# Mirtle_Teensy3_ESP_2016_Hotec6c.net
KiCad netlist of a schematic drawn in EAGLE
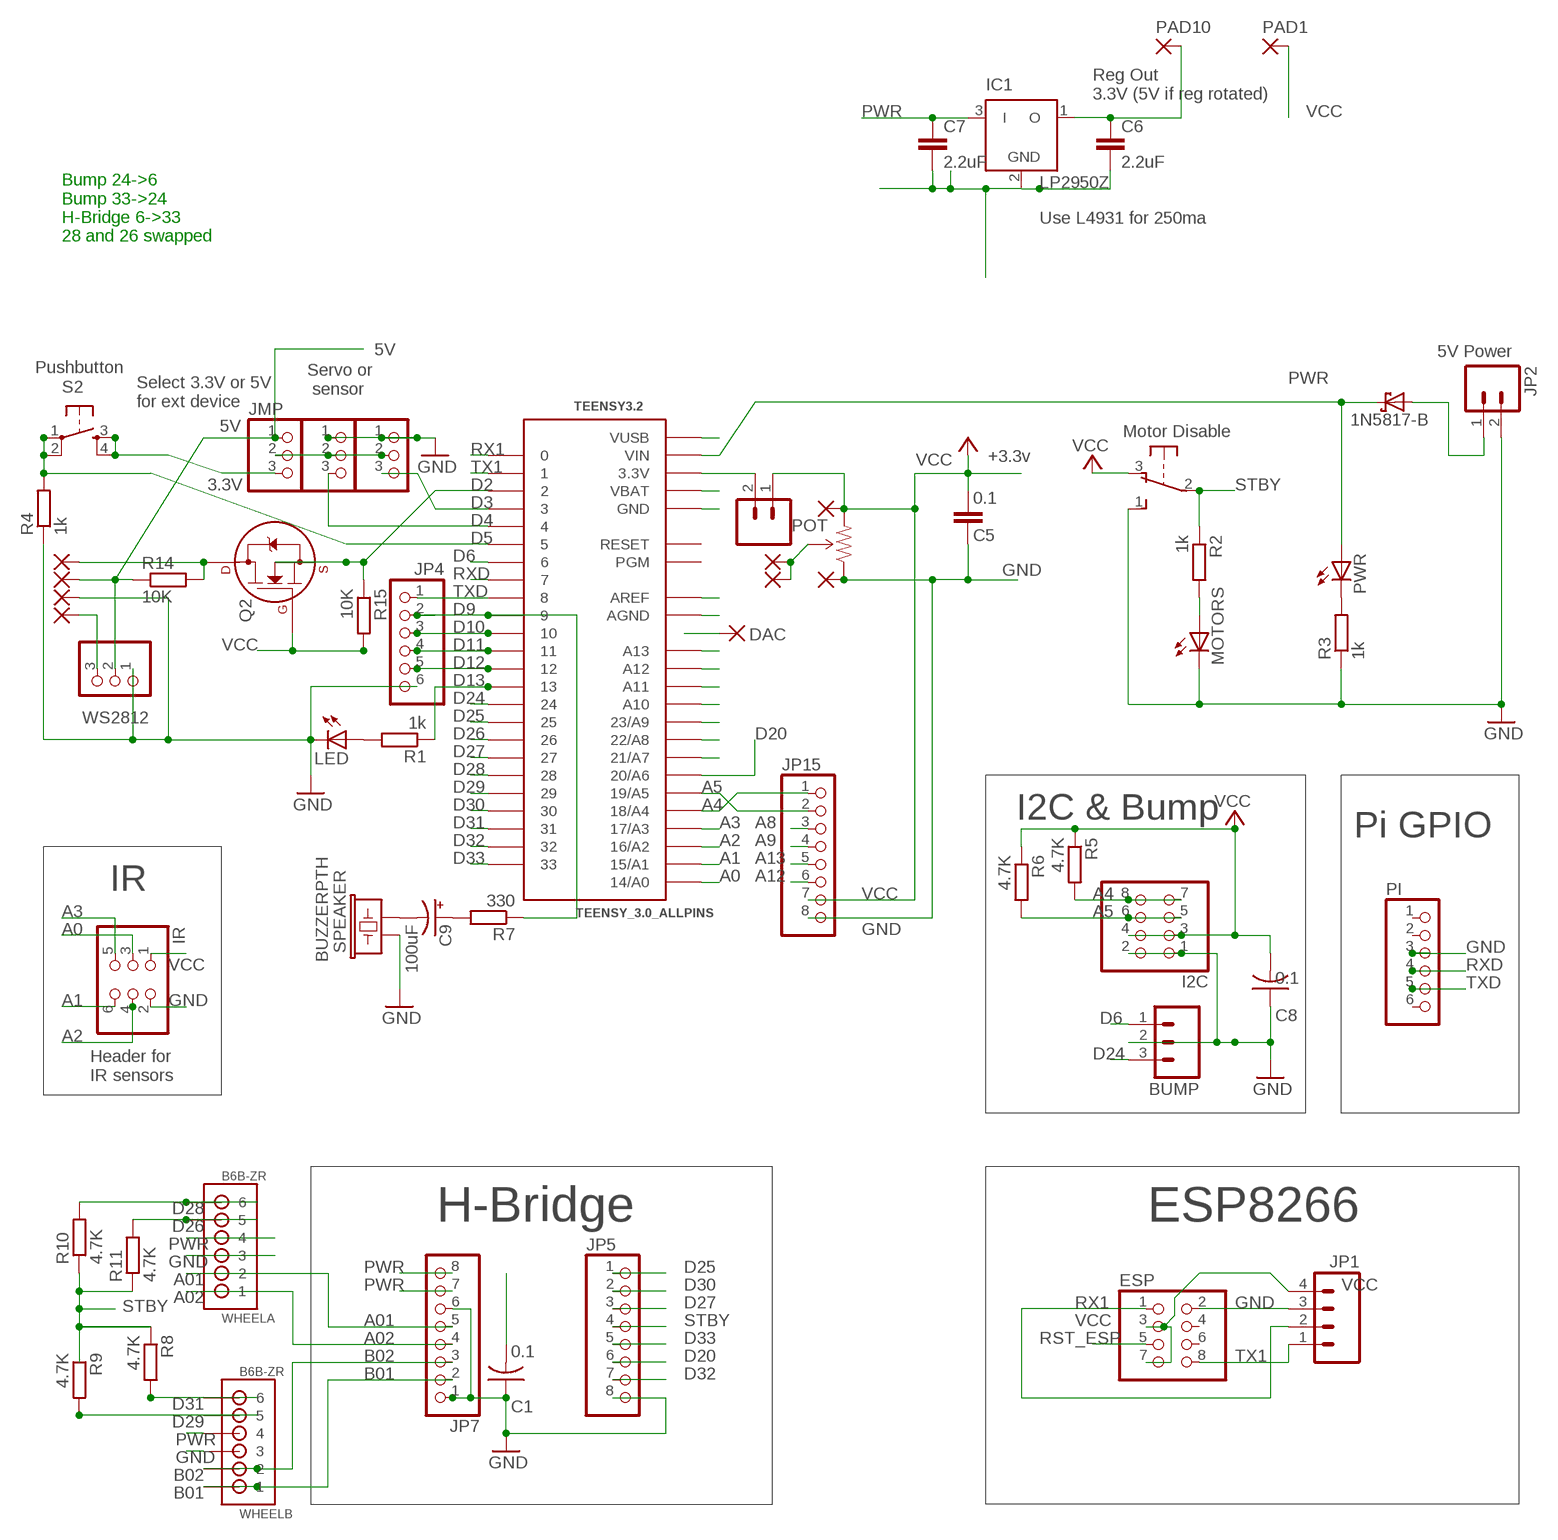
[diagram p0: schematic, sheet 1]

(export (version "E")
  (design (tool "Eeschema 10.0.6"))
  (components
    (comp (ref "3V3")
      (value "M02PTH")
      (footprint "eagle-import:1X02")
      (libsource (lib "eagle-import") (part "M02PTH"))
    )
    (comp (ref "BUMP")
      (value "M03SCREW")
      (footprint "eagle-import:SCREWTERMINAL-3.5MM-3")
      (libsource (lib "eagle-import") (part "M03SCREW"))
    )
    (comp (ref "C1")
      (value "0.1")
      (footprint "eagle-import:C025-024X044")
      (libsource (lib "eagle-import") (part "C-US025-024X044"))
    )
    (comp (ref "C5")
      (value "0.1")
      (footprint "eagle-import:CAP-PTH-SMALLEZ")
      (libsource (lib "eagle-import") (part "CAPEZ"))
    )
    (comp (ref "C6")
      (value "2.2uF")
      (footprint "eagle-import:C050-024X044")
      (libsource (lib "eagle-import") (part "C-EU050-024X044"))
    )
    (comp (ref "C7")
      (value "2.2uF")
      (footprint "eagle-import:C050-024X044")
      (libsource (lib "eagle-import") (part "C-EU050-024X044"))
    )
    (comp (ref "C8")
      (value "0.1")
      (footprint "eagle-import:C025-024X044")
      (libsource (lib "eagle-import") (part "C-US025-024X044"))
    )
    (comp (ref "C9")
      (value "100uF")
      (footprint "eagle-import:E2,5-5")
      (libsource (lib "eagle-import") (part "CPOL-USE2.5-5"))
    )
    (comp (ref "D1")
      (value "1N5817-B")
      (footprint "eagle-import:DO41-7.6")
      (libsource (lib "eagle-import") (part "1N5817-B"))
    )
    (comp (ref "DAC")
      (value "1,6/0,8")
      (footprint "eagle-import:1,6_0,8")
      (libsource (lib "eagle-import") (part "1,6/0,8"))
    )
    (comp (ref "ESP")
      (value "PINHD-2X4")
      (footprint "eagle-import:2X04")
      (libsource (lib "eagle-import") (part "adafruit_mem_PINHD-2X4"))
    )
    (comp (ref "EXT")
      (value "PINHD-1X3")
      (footprint "eagle-import:1X03")
      (libsource (lib "eagle-import") (part "PINHD-1X3"))
    )
    (comp (ref "EXT1")
      (value "PINHD-1X3")
      (footprint "eagle-import:1X03")
      (libsource (lib "eagle-import") (part "PINHD-1X3"))
    )
    (comp (ref "I2C")
      (value "PINHD-2X4")
      (footprint "eagle-import:2X04")
      (libsource (lib "eagle-import") (part "PINHD-2X4"))
    )
    (comp (ref "IC1")
      (value "LP2950Z")
      (footprint "eagle-import:TO92")
      (libsource (lib "eagle-import") (part "LP2950Z"))
    )
    (comp (ref "IR")
      (value "PINHD-2X3")
      (footprint "eagle-import:2X03")
      (libsource (lib "eagle-import") (part "PINHD-2X3"))
    )
    (comp (ref "JMP")
      (value "PINHD-1X3")
      (footprint "eagle-import:1X03")
      (libsource (lib "eagle-import") (part "PINHD-1X3"))
    )
    (comp (ref "JP1")
      (value "M04PTH")
      (footprint "eagle-import:1X04")
      (libsource (lib "eagle-import") (part "M04PTH"))
    )
    (comp (ref "JP2")
      (value "M023.5MM")
      (footprint "eagle-import:SCREWTERMINAL-3.5MM-2")
      (libsource (lib "eagle-import") (part "M023.5MM"))
    )
    (comp (ref "JP4")
      (value "PINHD-1X6B")
      (footprint "eagle-import:1X06-BIG")
      (libsource (lib "eagle-import") (part "PINHD-1X6B"))
    )
    (comp (ref "JP5")
      (value "PINHD-1X8CLEANBIG")
      (footprint "eagle-import:1X08-CLEANBIG")
      (libsource (lib "eagle-import") (part "PINHD-1X8CLEANBIG"))
    )
    (comp (ref "JP7")
      (value "PINHD-1X8CLEANBIG")
      (footprint "eagle-import:1X08-CLEANBIG")
      (libsource (lib "eagle-import") (part "PINHD-1X8CLEANBIG"))
    )
    (comp (ref "JP15")
      (value "PINHD-1X8BIG")
      (footprint "eagle-import:1X08-BIG")
      (libsource (lib "eagle-import") (part "PINHD-1X8BIG"))
    )
    (comp (ref "LED")
      (value "LED3MM")
      (footprint "eagle-import:LED3MM")
      (libsource (lib "eagle-import") (part "LED3MM"))
    )
    (comp (ref "MOTORS")
      (value "LED3MM")
      (footprint "eagle-import:LED3MM")
      (libsource (lib "eagle-import") (part "LED3MM"))
    )
    (comp (ref "PAD1")
      (value "1,6/0,8")
      (footprint "eagle-import:1,6_0,8")
      (libsource (lib "eagle-import") (part "1,6/0,8"))
    )
    (comp (ref "PAD2")
      (value "1,6/0,8")
      (footprint "eagle-import:1,6_0,8")
      (libsource (lib "eagle-import") (part "1,6/0,8"))
    )
    (comp (ref "PAD3")
      (value "1,6/0,8")
      (footprint "eagle-import:1,6_0,8")
      (libsource (lib "eagle-import") (part "1,6/0,8"))
    )
    (comp (ref "PAD4")
      (value "1,6/0,8")
      (footprint "eagle-import:1,6_0,8")
      (libsource (lib "eagle-import") (part "1,6/0,8"))
    )
    (comp (ref "PAD5")
      (value "1,6/0,8")
      (footprint "eagle-import:1,6_0,8")
      (libsource (lib "eagle-import") (part "1,6/0,8"))
    )
    (comp (ref "PAD6")
      (value "1,6/0,8")
      (footprint "eagle-import:1,6_0,8")
      (libsource (lib "eagle-import") (part "1,6/0,8"))
    )
    (comp (ref "PAD7")
      (value "1,6/0,8")
      (footprint "eagle-import:1,6_0,8")
      (libsource (lib "eagle-import") (part "1,6/0,8"))
    )
    (comp (ref "PAD8")
      (value "1,6/0,8")
      (footprint "eagle-import:1,6_0,8")
      (libsource (lib "eagle-import") (part "1,6/0,8"))
    )
    (comp (ref "PAD9")
      (value "1,6/0,8")
      (footprint "eagle-import:1,6_0,8")
      (libsource (lib "eagle-import") (part "1,6/0,8"))
    )
    (comp (ref "PAD10")
      (value "1,6/0,8")
      (footprint "eagle-import:1,6_0,8")
      (libsource (lib "eagle-import") (part "1,6/0,8"))
    )
    (comp (ref "PI")
      (value "PINHD-1X6")
      (footprint "eagle-import:1X06")
      (libsource (lib "eagle-import") (part "PINHD-1X6"))
    )
    (comp (ref "POT")
      (value "TSR-3386")
      (footprint "eagle-import:3386U")
      (libsource (lib "eagle-import") (part "TRIMPOT-PTH-KNOB"))
    )
    (comp (ref "PWR")
      (value "LED3MM")
      (footprint "eagle-import:LED3MM")
      (libsource (lib "eagle-import") (part "LED3MM"))
    )
    (comp (ref "Q2")
      (value "2N7000_TO92")
      (footprint "eagle-import:TO-92")
      (libsource (lib "eagle-import") (part "2N700_TO920"))
    )
    (comp (ref "R1")
      (value "1k")
      (footprint "eagle-import:0204_7")
      (libsource (lib "eagle-import") (part "R-EU_0204/7"))
    )
    (comp (ref "R2")
      (value "1k")
      (footprint "eagle-import:0204_7")
      (libsource (lib "eagle-import") (part "R-EU_0204/7"))
    )
    (comp (ref "R3")
      (value "1k")
      (footprint "eagle-import:0204_7")
      (libsource (lib "eagle-import") (part "R-EU_0204/7"))
    )
    (comp (ref "R4")
      (value "1k")
      (footprint "eagle-import:0204_7")
      (libsource (lib "eagle-import") (part "R-EU_0204/7"))
    )
    (comp (ref "R5")
      (value "4.7K")
      (footprint "eagle-import:0204_7")
      (libsource (lib "eagle-import") (part "R-EU_0204/7"))
    )
    (comp (ref "R6")
      (value "4.7K")
      (footprint "eagle-import:0204_7")
      (libsource (lib "eagle-import") (part "R-EU_0204/7"))
    )
    (comp (ref "R7")
      (value "330")
      (footprint "eagle-import:0204_7")
      (libsource (lib "eagle-import") (part "R-EU_0204/7"))
    )
    (comp (ref "R8")
      (value "4.7K")
      (footprint "eagle-import:0204_5")
      (libsource (lib "eagle-import") (part "R-EU_0204/5"))
    )
    (comp (ref "R9")
      (value "4.7K")
      (footprint "eagle-import:0204_5")
      (libsource (lib "eagle-import") (part "R-EU_0204/5"))
    )
    (comp (ref "R10")
      (value "4.7K")
      (footprint "eagle-import:0204_5")
      (libsource (lib "eagle-import") (part "R-EU_0204/5"))
    )
    (comp (ref "R11")
      (value "4.7K")
      (footprint "eagle-import:0204_5")
      (libsource (lib "eagle-import") (part "R-EU_0204/5"))
    )
    (comp (ref "R14")
      (value "10K")
      (footprint "eagle-import:0204_5")
      (libsource (lib "eagle-import") (part "R-EU_0204/5"))
    )
    (comp (ref "R15")
      (value "10K")
      (footprint "eagle-import:0204_5")
      (libsource (lib "eagle-import") (part "R-EU_0204/5"))
    )
    (comp (ref "S2")
      (value "TAC_SWITCHPTH")
      (footprint "eagle-import:TACTILE-PTH")
      (libsource (lib "eagle-import") (part "TAC_SWITCHPTH"))
    )
    (comp (ref "SPEAKER")
      (value "BUZZERPTH")
      (footprint "eagle-import:BUZZER-12MM")
      (libsource (lib "eagle-import") (part "BUZZERPTH"))
    )
    (comp (ref "SW1")
      (value "OS102011MA1Q")
      (footprint "eagle-import:OS102011MA1Q")
      (libsource (lib "eagle-import") (part "OS102011MA1Q"))
    )
    (comp (ref "TEENSY3.2")
      (value "TEENSY_3.0_ALLPINS")
      (footprint "eagle-import:TEENSY_3.0_ALLPINS")
      (libsource (lib "eagle-import") (part "TEENSY_3.0_ALLPINS"))
    )
    (comp (ref "WHEELA")
      (value "B6B-ZR")
      (footprint "eagle-import:B6B-ZR")
      (libsource (lib "eagle-import") (part "B6B-ZR"))
    )
    (comp (ref "WHEELB")
      (value "B6B-ZR")
      (footprint "eagle-import:B6B-ZR")
      (libsource (lib "eagle-import") (part "B6B-ZR"))
    )
    (comp (ref "WS2812")
      (value "PINHD-1X3")
      (footprint "eagle-import:1X03")
      (libsource (lib "eagle-import") (part "PINHD-1X3"))
    )
  )
  (nets
    (net (code "1") (name "/5VIN") (class "Default")
      (node (ref "C1") (pin "2") (pinfunction "2_2") (pintype "passive"))
      (node (ref "D1") (pin "A") (pinfunction "A_A") (pintype "passive"))
      (node (ref "JP2") (pin "1") (pinfunction "1_1") (pintype "passive"))
    )
    (net (code "2") (name "/A0") (class "Default")
      (node (ref "IR") (pin "3") (pinfunction "3_3") (pintype "passive"))
      (node (ref "TEENSY3.2") (pin "14/A0") (pinfunction "14/A0_14/A0") (pintype "bidirectional"))
    )
    (net (code "3") (name "/A01") (class "Default")
      (node (ref "JP7") (pin "5") (pinfunction "5_5") (pintype "passive"))
      (node (ref "WHEELA") (pin "2") (pinfunction "2_2") (pintype "bidirectional"))
    )
    (net (code "4") (name "/A1") (class "Default")
      (node (ref "IR") (pin "6") (pinfunction "6_6") (pintype "passive"))
      (node (ref "TEENSY3.2") (pin "15/A1") (pinfunction "15/A1_15/A1") (pintype "bidirectional"))
    )
    (net (code "5") (name "/A02") (class "Default")
      (node (ref "JP7") (pin "4") (pinfunction "4_4") (pintype "passive"))
      (node (ref "WHEELA") (pin "1") (pinfunction "1_1") (pintype "bidirectional"))
    )
    (net (code "6") (name "/A2") (class "Default")
      (node (ref "IR") (pin "4") (pinfunction "4_4") (pintype "passive"))
      (node (ref "TEENSY3.2") (pin "16/A2") (pinfunction "16/A2_16/A2") (pintype "bidirectional"))
    )
    (net (code "7") (name "/A3") (class "Default")
      (node (ref "IR") (pin "5") (pinfunction "5_5") (pintype "passive"))
      (node (ref "TEENSY3.2") (pin "17/A3") (pinfunction "17/A3_17/A3") (pintype "bidirectional"))
    )
    (net (code "8") (name "/A4") (class "Default")
      (node (ref "I2C") (pin "7") (pinfunction "7_7") (pintype "passive"))
      (node (ref "I2C") (pin "8") (pinfunction "8_8") (pintype "passive"))
      (node (ref "JP15") (pin "1") (pinfunction "1_1") (pintype "passive"))
      (node (ref "R5") (pin "2") (pinfunction "2_2") (pintype "passive"))
      (node (ref "TEENSY3.2") (pin "18/A4") (pinfunction "18/A4_18/A4") (pintype "bidirectional"))
    )
    (net (code "9") (name "/A5") (class "Default")
      (node (ref "I2C") (pin "5") (pinfunction "5_5") (pintype "passive"))
      (node (ref "I2C") (pin "6") (pinfunction "6_6") (pintype "passive"))
      (node (ref "JP15") (pin "2") (pinfunction "2_2") (pintype "passive"))
      (node (ref "R6") (pin "2") (pinfunction "2_2") (pintype "passive"))
      (node (ref "TEENSY3.2") (pin "19/A5") (pinfunction "19/A5_19/A5") (pintype "bidirectional"))
    )
    (net (code "10") (name "/A7") (class "Default")
      (node (ref "PAD6") (pin "1") (pinfunction "P_1") (pintype "passive"))
      (node (ref "PAD9") (pin "1") (pinfunction "P_1") (pintype "passive"))
      (node (ref "POT") (pin "2") (pinfunction "WIPER_2") (pintype "passive"))
      (node (ref "TEENSY3.2") (pin "21/A7") (pinfunction "21/A7_21/A7") (pintype "bidirectional"))
    )
    (net (code "11") (name "/A8") (class "Default")
      (node (ref "JP15") (pin "3") (pinfunction "3_3") (pintype "passive"))
      (node (ref "TEENSY3.2") (pin "22/A8") (pinfunction "22/A8_22/A8") (pintype "bidirectional"))
    )
    (net (code "12") (name "/A9") (class "Default")
      (node (ref "JP15") (pin "4") (pinfunction "4_4") (pintype "passive"))
      (node (ref "TEENSY3.2") (pin "23/A9") (pinfunction "23/A9_23/A9") (pintype "bidirectional"))
    )
    (net (code "13") (name "/A12") (class "Default")
      (node (ref "JP15") (pin "6") (pinfunction "6_6") (pintype "passive"))
      (node (ref "TEENSY3.2") (pin "A12") (pinfunction "A12_A12") (pintype "bidirectional"))
    )
    (net (code "14") (name "/A13") (class "Default")
      (node (ref "JP15") (pin "5") (pinfunction "5_5") (pintype "passive"))
      (node (ref "TEENSY3.2") (pin "A13") (pinfunction "A13_A13") (pintype "bidirectional"))
    )
    (net (code "15") (name "/B01") (class "Default")
      (node (ref "JP7") (pin "2") (pinfunction "2_2") (pintype "passive"))
      (node (ref "WHEELB") (pin "1") (pinfunction "1_1") (pintype "bidirectional"))
    )
    (net (code "16") (name "/B02") (class "Default")
      (node (ref "JP7") (pin "3") (pinfunction "3_3") (pintype "passive"))
      (node (ref "WHEELB") (pin "2") (pinfunction "2_2") (pintype "bidirectional"))
    )
    (net (code "17") (name "/D2") (class "Default")
      (node (ref "Q2") (pin "1") (pinfunction "S_1") (pintype "bidirectional"))
      (node (ref "R15") (pin "1") (pinfunction "1_1") (pintype "passive"))
      (node (ref "TEENSY3.2") (pin "2") (pinfunction "2_2") (pintype "bidirectional"))
    )
    (net (code "18") (name "/D3") (class "Default")
      (node (ref "EXT") (pin "3") (pinfunction "3_3") (pintype "passive"))
      (node (ref "TEENSY3.2") (pin "3") (pinfunction "3_3") (pintype "bidirectional"))
    )
    (net (code "19") (name "/D4") (class "Default")
      (node (ref "EXT1") (pin "3") (pinfunction "3_3") (pintype "passive"))
      (node (ref "TEENSY3.2") (pin "4") (pinfunction "4_4") (pintype "bidirectional"))
    )
    (net (code "20") (name "/D5") (class "Default")
      (node (ref "R4") (pin "2") (pinfunction "2_2") (pintype "passive"))
      (node (ref "S2") (pin "1") (pinfunction "1_1") (pintype "passive"))
      (node (ref "S2") (pin "2") (pinfunction "2_2") (pintype "passive"))
      (node (ref "TEENSY3.2") (pin "5") (pinfunction "5_5") (pintype "bidirectional"))
    )
    (net (code "21") (name "/D6") (class "Default")
      (node (ref "BUMP") (pin "1") (pinfunction "1_1") (pintype "passive"))
      (node (ref "TEENSY3.2") (pin "6") (pinfunction "6_6") (pintype "bidirectional"))
    )
    (net (code "22") (name "/D9") (class "Default")
      (node (ref "JP4") (pin "2") (pinfunction "2_2") (pintype "passive"))
      (node (ref "R7") (pin "1") (pinfunction "1_1") (pintype "passive"))
      (node (ref "TEENSY3.2") (pin "9") (pinfunction "9_9") (pintype "bidirectional"))
    )
    (net (code "23") (name "/D10") (class "Default")
      (node (ref "JP4") (pin "3") (pinfunction "3_3") (pintype "passive"))
      (node (ref "TEENSY3.2") (pin "10") (pinfunction "10_10") (pintype "bidirectional"))
    )
    (net (code "24") (name "/D11") (class "Default")
      (node (ref "JP4") (pin "4") (pinfunction "4_4") (pintype "passive"))
      (node (ref "TEENSY3.2") (pin "11") (pinfunction "11_11") (pintype "bidirectional"))
    )
    (net (code "25") (name "/D12") (class "Default")
      (node (ref "JP4") (pin "5") (pinfunction "5_5") (pintype "passive"))
      (node (ref "TEENSY3.2") (pin "12") (pinfunction "12_12") (pintype "bidirectional"))
    )
    (net (code "26") (name "/D13") (class "Default")
      (node (ref "R1") (pin "1") (pinfunction "1_1") (pintype "passive"))
      (node (ref "TEENSY3.2") (pin "13") (pinfunction "13_13") (pintype "bidirectional"))
    )
    (net (code "27") (name "/D20") (class "Default")
      (node (ref "JP5") (pin "6") (pinfunction "6_6") (pintype "passive"))
      (node (ref "TEENSY3.2") (pin "20/A6") (pinfunction "20/A6_20/A6") (pintype "bidirectional"))
    )
    (net (code "28") (name "/D24") (class "Default")
      (node (ref "BUMP") (pin "3") (pinfunction "3_3") (pintype "passive"))
      (node (ref "TEENSY3.2") (pin "24") (pinfunction "24_24") (pintype "bidirectional"))
    )
    (net (code "29") (name "/D25") (class "Default")
      (node (ref "JP5") (pin "1") (pinfunction "1_1") (pintype "passive"))
      (node (ref "TEENSY3.2") (pin "25") (pinfunction "25_25") (pintype "bidirectional"))
    )
    (net (code "30") (name "/D26") (class "Default")
      (node (ref "R11") (pin "2") (pinfunction "2_2") (pintype "passive"))
      (node (ref "TEENSY3.2") (pin "26") (pinfunction "26_26") (pintype "bidirectional"))
      (node (ref "WHEELA") (pin "5") (pinfunction "5_5") (pintype "bidirectional"))
    )
    (net (code "31") (name "/D27") (class "Default")
      (node (ref "JP5") (pin "3") (pinfunction "3_3") (pintype "passive"))
      (node (ref "TEENSY3.2") (pin "27") (pinfunction "27_27") (pintype "bidirectional"))
    )
    (net (code "32") (name "/D28") (class "Default")
      (node (ref "R10") (pin "2") (pinfunction "2_2") (pintype "passive"))
      (node (ref "TEENSY3.2") (pin "28") (pinfunction "28_28") (pintype "bidirectional"))
      (node (ref "WHEELA") (pin "6") (pinfunction "6_6") (pintype "bidirectional"))
    )
    (net (code "33") (name "/D29") (class "Default")
      (node (ref "R9") (pin "2") (pinfunction "2_2") (pintype "passive"))
      (node (ref "TEENSY3.2") (pin "29") (pinfunction "29_29") (pintype "bidirectional"))
      (node (ref "WHEELB") (pin "5") (pinfunction "5_5") (pintype "bidirectional"))
    )
    (net (code "34") (name "/D30") (class "Default")
      (node (ref "JP5") (pin "2") (pinfunction "2_2") (pintype "passive"))
      (node (ref "TEENSY3.2") (pin "30") (pinfunction "30_30") (pintype "bidirectional"))
    )
    (net (code "35") (name "/D31") (class "Default")
      (node (ref "R8") (pin "2") (pinfunction "2_2") (pintype "passive"))
      (node (ref "TEENSY3.2") (pin "31") (pinfunction "31_31") (pintype "bidirectional"))
      (node (ref "WHEELB") (pin "6") (pinfunction "6_6") (pintype "bidirectional"))
    )
    (net (code "36") (name "/D32") (class "Default")
      (node (ref "JP5") (pin "7") (pinfunction "7_7") (pintype "passive"))
      (node (ref "TEENSY3.2") (pin "32") (pinfunction "32_32") (pintype "bidirectional"))
    )
    (net (code "37") (name "/D33") (class "Default")
      (node (ref "JP5") (pin "5") (pinfunction "5_5") (pintype "passive"))
      (node (ref "TEENSY3.2") (pin "33") (pinfunction "33_33") (pintype "bidirectional"))
    )
    (net (code "38") (name "/PWR") (class "Default")
      (node (ref "C7") (pin "1") (pinfunction "1_1") (pintype "passive"))
      (node (ref "D1") (pin "C") (pinfunction "C_C") (pintype "passive"))
      (node (ref "IC1") (pin "3") (pinfunction "I_3") (pintype "input"))
      (node (ref "JMP") (pin "1") (pinfunction "1_1") (pintype "passive"))
      (node (ref "JP7") (pin "7") (pinfunction "7_7") (pintype "passive"))
      (node (ref "JP7") (pin "8") (pinfunction "8_8") (pintype "passive"))
      (node (ref "PAD3") (pin "1") (pinfunction "P_1") (pintype "passive"))
      (node (ref "PWR") (pin "A") (pinfunction "A_A") (pintype "passive"))
      (node (ref "R14") (pin "1") (pinfunction "1_1") (pintype "passive"))
      (node (ref "TEENSY3.2") (pin "VIN") (pinfunction "VIN_VIN") (pintype "power_in"))
      (node (ref "WHEELA") (pin "4") (pinfunction "4_4") (pintype "bidirectional"))
      (node (ref "WHEELB") (pin "4") (pinfunction "4_4") (pintype "bidirectional"))
      (node (ref "WS2812") (pin "2") (pinfunction "2_2") (pintype "passive"))
    )
    (net (code "39") (name "/RST_ESP") (class "Default")
      (node (ref "ESP") (pin "5") (pinfunction "5_5") (pintype "passive"))
    )
    (net (code "40") (name "/RX1") (class "Default")
      (node (ref "ESP") (pin "1") (pinfunction "1_1") (pintype "passive"))
      (node (ref "JP1") (pin "2") (pinfunction "2_2") (pintype "passive"))
      (node (ref "TEENSY3.2") (pin "0") (pinfunction "0_0") (pintype "bidirectional"))
    )
    (net (code "41") (name "/RXD") (class "Default")
      (node (ref "PI") (pin "4") (pinfunction "4_4") (pintype "passive"))
      (node (ref "TEENSY3.2") (pin "7") (pinfunction "7_7") (pintype "bidirectional"))
    )
    (net (code "42") (name "/STBY") (class "Default")
      (node (ref "JP5") (pin "4") (pinfunction "4_4") (pintype "passive"))
      (node (ref "R10") (pin "1") (pinfunction "1_1") (pintype "passive"))
      (node (ref "R11") (pin "1") (pinfunction "1_1") (pintype "passive"))
      (node (ref "R2") (pin "1") (pinfunction "1_1") (pintype "passive"))
      (node (ref "R8") (pin "1") (pinfunction "1_1") (pintype "passive"))
      (node (ref "R9") (pin "1") (pinfunction "1_1") (pintype "passive"))
      (node (ref "SW1") (pin "2") (pinfunction "P_2") (pintype "passive"))
    )
    (net (code "43") (name "/TX1") (class "Default")
      (node (ref "ESP") (pin "8") (pinfunction "8_8") (pintype "passive"))
      (node (ref "JP1") (pin "1") (pinfunction "1_1") (pintype "passive"))
      (node (ref "TEENSY3.2") (pin "1") (pinfunction "1_1") (pintype "bidirectional"))
    )
    (net (code "44") (name "/TXD") (class "Default")
      (node (ref "JP4") (pin "1") (pinfunction "1_1") (pintype "passive"))
      (node (ref "PI") (pin "5") (pinfunction "5_5") (pintype "passive"))
      (node (ref "TEENSY3.2") (pin "8") (pinfunction "8_8") (pintype "bidirectional"))
    )
    (net (code "45") (name "GND") (class "Default")
      (node (ref "BUMP") (pin "2") (pinfunction "2_2") (pintype "passive"))
      (node (ref "C1") (pin "1") (pinfunction "1_1") (pintype "passive"))
      (node (ref "C5") (pin "1") (pinfunction "1_1") (pintype "passive"))
      (node (ref "C6") (pin "2") (pinfunction "2_2") (pintype "passive"))
      (node (ref "C7") (pin "2") (pinfunction "2_2") (pintype "passive"))
      (node (ref "C8") (pin "1") (pinfunction "1_1") (pintype "passive"))
      (node (ref "ESP") (pin "2") (pinfunction "2_2") (pintype "passive"))
      (node (ref "EXT") (pin "1") (pinfunction "1_1") (pintype "passive"))
      (node (ref "EXT1") (pin "1") (pinfunction "1_1") (pintype "passive"))
      (node (ref "I2C") (pin "1") (pinfunction "1_1") (pintype "passive"))
      (node (ref "I2C") (pin "2") (pinfunction "2_2") (pintype "passive"))
      (node (ref "IC1") (pin "2") (pinfunction "GND_2") (pintype "power_in"))
      (node (ref "IR") (pin "2") (pinfunction "2_2") (pintype "passive"))
      (node (ref "JP1") (pin "3") (pinfunction "3_3") (pintype "passive"))
      (node (ref "JP15") (pin "8") (pinfunction "8_8") (pintype "passive"))
      (node (ref "JP2") (pin "2") (pinfunction "2_2") (pintype "passive"))
      (node (ref "JP4") (pin "6") (pinfunction "6_6") (pintype "passive"))
      (node (ref "JP5") (pin "8") (pinfunction "8_8") (pintype "passive"))
      (node (ref "JP7") (pin "1") (pinfunction "1_1") (pintype "passive"))
      (node (ref "JP7") (pin "6") (pinfunction "6_6") (pintype "passive"))
      (node (ref "LED") (pin "K") (pinfunction "C_K") (pintype "passive"))
      (node (ref "MOTORS") (pin "K") (pinfunction "C_K") (pintype "passive"))
      (node (ref "PAD4") (pin "1") (pinfunction "P_1") (pintype "passive"))
      (node (ref "PAD8") (pin "1") (pinfunction "P_1") (pintype "passive"))
      (node (ref "PI") (pin "3") (pinfunction "3_3") (pintype "passive"))
      (node (ref "POT") (pin "1") (pinfunction "CCW_1") (pintype "passive"))
      (node (ref "R3") (pin "1") (pinfunction "1_1") (pintype "passive"))
      (node (ref "R4") (pin "1") (pinfunction "1_1") (pintype "passive"))
      (node (ref "SPEAKER") (pin "+") (pinfunction "1_+") (pintype "passive"))
      (node (ref "SW1") (pin "1") (pinfunction "S_1") (pintype "passive"))
      (node (ref "TEENSY3.2") (pin "AGND") (pinfunction "AGND_AGND") (pintype "power_in"))
      (node (ref "TEENSY3.2") (pin "GND") (pinfunction "GND_GND") (pintype "power_in"))
      (node (ref "TEENSY3.2") (pin "GND1") (pinfunction "GND_GND1") (pintype "power_in"))
      (node (ref "TEENSY3.2") (pin "GND2") (pinfunction "GND_GND2") (pintype "power_in"))
      (node (ref "WHEELA") (pin "3") (pinfunction "3_3") (pintype "bidirectional"))
      (node (ref "WHEELB") (pin "3") (pinfunction "3_3") (pintype "bidirectional"))
      (node (ref "WS2812") (pin "1") (pinfunction "1_1") (pintype "passive"))
    )
    (net (code "46") (name "Net-(3V3-Pad2)") (class "Default")
      (node (ref "3V3") (pin "2") (pinfunction "2_2") (pintype "passive"))
      (node (ref "TEENSY3.2") (pin "3.3V") (pinfunction "3.3V_3.3V") (pintype "power_in"))
      (node (ref "TEENSY3.2") (pin "3.3V1") (pinfunction "3.3V_3.3V1") (pintype "power_in"))
      (node (ref "TEENSY3.2") (pin "3.3V2") (pinfunction "3.3V_3.3V2") (pintype "power_in"))
    )
    (net (code "47") (name "Net-(C9-Pad+)") (class "Default")
      (node (ref "C9") (pin "+") (pinfunction "+_+") (pintype "passive"))
      (node (ref "R7") (pin "2") (pinfunction "2_2") (pintype "passive"))
    )
    (net (code "48") (name "Net-(EXT-Pad2)") (class "Default")
      (node (ref "EXT") (pin "2") (pinfunction "2_2") (pintype "passive"))
      (node (ref "EXT1") (pin "2") (pinfunction "2_2") (pintype "passive"))
      (node (ref "JMP") (pin "2") (pinfunction "2_2") (pintype "passive"))
    )
    (net (code "49") (name "Net-(IC1-O)") (class "Default")
      (node (ref "C6") (pin "1") (pinfunction "1_1") (pintype "passive"))
      (node (ref "IC1") (pin "1") (pinfunction "O_1") (pintype "input"))
      (node (ref "PAD10") (pin "1") (pinfunction "P_1") (pintype "passive"))
    )
    (net (code "50") (name "Net-(LED-PadA)") (class "Default")
      (node (ref "LED") (pin "A") (pinfunction "A_A") (pintype "passive"))
      (node (ref "R1") (pin "2") (pinfunction "2_2") (pintype "passive"))
    )
    (net (code "51") (name "Net-(MOTORS-PadA)") (class "Default")
      (node (ref "MOTORS") (pin "A") (pinfunction "A_A") (pintype "passive"))
      (node (ref "R2") (pin "2") (pinfunction "2_2") (pintype "passive"))
    )
    (net (code "52") (name "Net-(PAD2-P)") (class "Default")
      (node (ref "PAD2") (pin "1") (pinfunction "P_1") (pintype "passive"))
      (node (ref "Q2") (pin "3") (pinfunction "D_3") (pintype "bidirectional"))
      (node (ref "R14") (pin "2") (pinfunction "2_2") (pintype "passive"))
    )
    (net (code "53") (name "Net-(PAD5-P)") (class "Default")
      (node (ref "PAD5") (pin "1") (pinfunction "P_1") (pintype "passive"))
      (node (ref "WS2812") (pin "3") (pinfunction "3_3") (pintype "passive"))
    )
    (net (code "54") (name "Net-(PWR-C)") (class "Default")
      (node (ref "PWR") (pin "K") (pinfunction "C_K") (pintype "passive"))
      (node (ref "R3") (pin "2") (pinfunction "2_2") (pintype "passive"))
    )
    (net (code "55") (name "Net-(SPEAKER-2)") (class "Default")
      (node (ref "C9") (pin "-") (pinfunction "-_-") (pintype "passive"))
      (node (ref "SPEAKER") (pin "-") (pinfunction "2_-") (pintype "passive"))
    )
    (net (code "56") (name "VCC") (class "Default")
      (node (ref "3V3") (pin "1") (pinfunction "1_1") (pintype "passive"))
      (node (ref "C5") (pin "2") (pinfunction "2_2") (pintype "passive"))
      (node (ref "C8") (pin "2") (pinfunction "2_2") (pintype "passive"))
      (node (ref "ESP") (pin "3") (pinfunction "3_3") (pintype "passive"))
      (node (ref "ESP") (pin "7") (pinfunction "7_7") (pintype "passive"))
      (node (ref "I2C") (pin "3") (pinfunction "3_3") (pintype "passive"))
      (node (ref "I2C") (pin "4") (pinfunction "4_4") (pintype "passive"))
      (node (ref "IR") (pin "1") (pinfunction "1_1") (pintype "passive"))
      (node (ref "JMP") (pin "3") (pinfunction "3_3") (pintype "passive"))
      (node (ref "JP1") (pin "4") (pinfunction "4_4") (pintype "passive"))
      (node (ref "JP15") (pin "7") (pinfunction "7_7") (pintype "passive"))
      (node (ref "PAD1") (pin "1") (pinfunction "P_1") (pintype "passive"))
      (node (ref "PAD7") (pin "1") (pinfunction "P_1") (pintype "passive"))
      (node (ref "POT") (pin "3") (pinfunction "CW_3") (pintype "passive"))
      (node (ref "Q2") (pin "2") (pinfunction "G_2") (pintype "tri_state"))
      (node (ref "R15") (pin "2") (pinfunction "2_2") (pintype "passive"))
      (node (ref "R5") (pin "1") (pinfunction "1_1") (pintype "passive"))
      (node (ref "R6") (pin "1") (pinfunction "1_1") (pintype "passive"))
      (node (ref "S2") (pin "3") (pinfunction "3_3") (pintype "passive"))
      (node (ref "S2") (pin "4") (pinfunction "4_4") (pintype "passive"))
      (node (ref "SW1") (pin "3") (pinfunction "O_3") (pintype "passive"))
    )
    (net (code "57") (name "unconnected-(DAC-P-Pad1)") (class "Default")
      (node (ref "DAC") (pin "1") (pinfunction "P_1") (pintype "passive"))
    )
    (net (code "58") (name "unconnected-(ESP-Pad4)") (class "Default")
      (node (ref "ESP") (pin "4") (pinfunction "4_4") (pintype "passive"))
    )
    (net (code "59") (name "unconnected-(ESP-Pad6)") (class "Default")
      (node (ref "ESP") (pin "6") (pinfunction "6_6") (pintype "passive"))
    )
    (net (code "60") (name "unconnected-(PI-Pad1)") (class "Default")
      (node (ref "PI") (pin "1") (pinfunction "1_1") (pintype "passive"))
    )
    (net (code "61") (name "unconnected-(PI-Pad2)") (class "Default")
      (node (ref "PI") (pin "2") (pinfunction "2_2") (pintype "passive"))
    )
    (net (code "62") (name "unconnected-(PI-Pad6)") (class "Default")
      (node (ref "PI") (pin "6") (pinfunction "6_6") (pintype "passive"))
    )
    (net (code "63") (name "unconnected-(TEENSY3.2-PadA10)") (class "Default")
      (node (ref "TEENSY3.2") (pin "A10") (pinfunction "A10_A10") (pintype "bidirectional"))
    )
    (net (code "64") (name "unconnected-(TEENSY3.2-PadA11)") (class "Default")
      (node (ref "TEENSY3.2") (pin "A11") (pinfunction "A11_A11") (pintype "bidirectional"))
    )
    (net (code "65") (name "unconnected-(TEENSY3.2-PadAREF)") (class "Default")
      (node (ref "TEENSY3.2") (pin "AREF") (pinfunction "AREF_AREF") (pintype "power_in"))
    )
    (net (code "66") (name "unconnected-(TEENSY3.2-PadPGM)") (class "Default")
      (node (ref "TEENSY3.2") (pin "PGM") (pinfunction "PGM_PGM") (pintype "bidirectional"))
    )
    (net (code "67") (name "unconnected-(TEENSY3.2-PadRESET)") (class "Default")
      (node (ref "TEENSY3.2") (pin "RESET") (pinfunction "RESET_RESET") (pintype "bidirectional"))
    )
    (net (code "68") (name "unconnected-(TEENSY3.2-PadVBAT)") (class "Default")
      (node (ref "TEENSY3.2") (pin "VBAT") (pinfunction "VBAT_VBAT") (pintype "power_in"))
    )
    (net (code "69") (name "unconnected-(TEENSY3.2-PadVUSB)") (class "Default")
      (node (ref "TEENSY3.2") (pin "VUSB") (pinfunction "VUSB_VUSB") (pintype "power_in"))
    )
  )
)
